# I2C-NIXIE-CTRL.net
KiCad netlist of a schematic drawn in Altium Designer
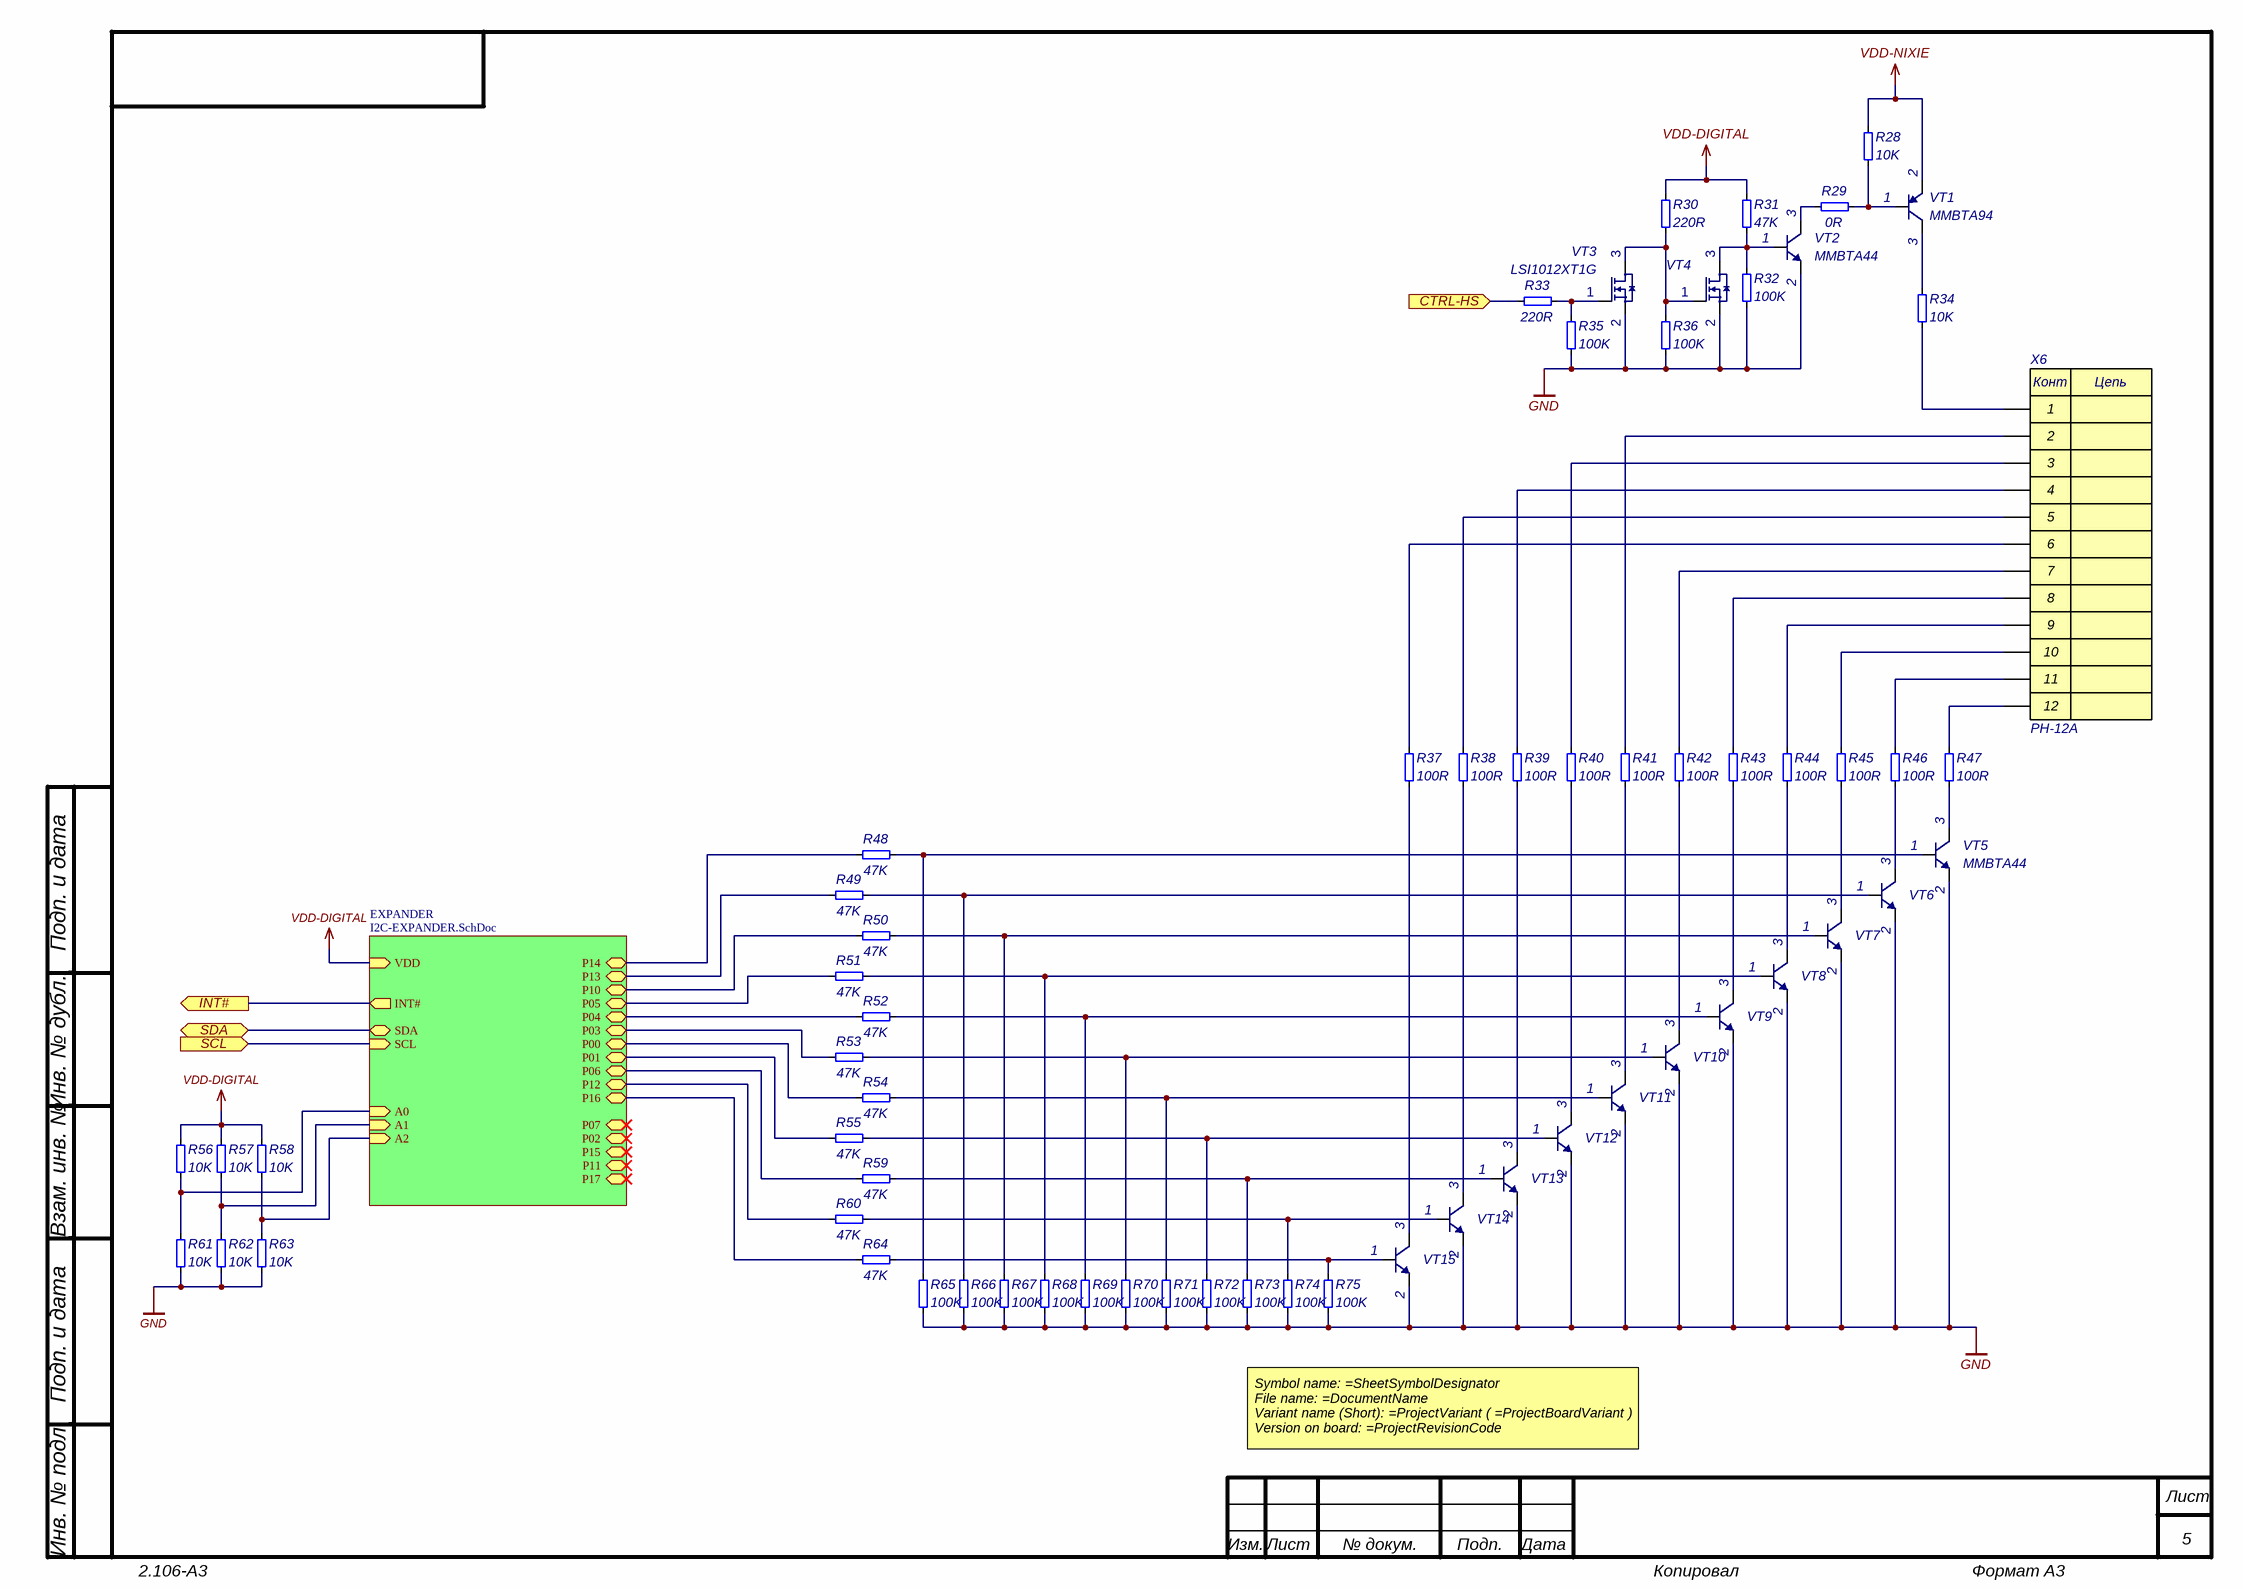
[diagram p0: I2C-NIXIE-CTRL.SchDoc]

(export (version "E")
  (design (tool "Eeschema 10.0.6"))
  (components
    (comp (ref "R28")
      (value "10K")
      (footprint "R_0805")
      (fields
        (field (name "PART NUMBER") "0805-0.125W-10K-200ppm±1%")
        (field (name "TOLERANCE") "1%")
        (field (name "MANUFACTURER") "Yageo")
      )
      (libsource (lib "ATB") (part "R"))
    )
    (comp (ref "R29")
      (value "0R")
      (footprint "R_0805")
      (fields
        (field (name "PART NUMBER") "0805-0.125W-0R-250ppm±5%")
        (field (name "TOLERANCE") "5%")
        (field (name "MANUFACTURER") "Yageo")
      )
      (libsource (lib "ATB") (part "R"))
    )
    (comp (ref "R30")
      (value "220R")
      (footprint "R_0402")
      (fields
        (field (name "PART NUMBER") "0402-0.0625W-220R-100ppm±1%")
        (field (name "TOLERANCE") "1%")
        (field (name "MANUFACTURER") "Yageo")
      )
      (libsource (lib "ATB") (part "R"))
    )
    (comp (ref "R31")
      (value "47K")
      (footprint "R_0402")
      (fields
        (field (name "PART NUMBER") "0402-0.0625W-47K-100ppm±1%")
        (field (name "TOLERANCE") "1%")
        (field (name "MANUFACTURER") "Yageo")
      )
      (libsource (lib "ATB") (part "R"))
    )
    (comp (ref "R32")
      (value "100K")
      (footprint "R_0402")
      (fields
        (field (name "PART NUMBER") "0402-0.0625W-100K-100ppm±1%")
        (field (name "TOLERANCE") "1%")
        (field (name "MANUFACTURER") "Yageo")
      )
      (libsource (lib "ATB") (part "R"))
    )
    (comp (ref "R33")
      (value "220R")
      (footprint "R_0402")
      (fields
        (field (name "PART NUMBER") "0402-0.0625W-220R-100ppm±1%")
        (field (name "TOLERANCE") "1%")
        (field (name "MANUFACTURER") "Yageo")
      )
      (libsource (lib "ATB") (part "R"))
    )
    (comp (ref "R34")
      (value "10K")
      (footprint "R_0805")
      (fields
        (field (name "PART NUMBER") "0805-0.125W-10K-200ppm±1%")
        (field (name "TOLERANCE") "1%")
        (field (name "MANUFACTURER") "Yageo")
      )
      (libsource (lib "ATB") (part "R"))
    )
    (comp (ref "R35")
      (value "100K")
      (footprint "R_0402")
      (fields
        (field (name "PART NUMBER") "0402-0.0625W-100K-100ppm±1%")
        (field (name "TOLERANCE") "1%")
        (field (name "MANUFACTURER") "Yageo")
      )
      (libsource (lib "ATB") (part "R"))
    )
    (comp (ref "R36")
      (value "100K")
      (footprint "R_0402")
      (fields
        (field (name "PART NUMBER") "0402-0.0625W-100K-100ppm±1%")
        (field (name "TOLERANCE") "1%")
        (field (name "MANUFACTURER") "Yageo")
      )
      (libsource (lib "ATB") (part "R"))
    )
    (comp (ref "R37")
      (value "100R")
      (footprint "R_0805")
      (fields
        (field (name "PART NUMBER") "0805-0.125W-100R-100ppm±1%")
        (field (name "TOLERANCE") "1%")
        (field (name "MANUFACTURER") "Yageo")
      )
      (libsource (lib "ATB") (part "R"))
    )
    (comp (ref "R38")
      (value "100R")
      (footprint "R_0805")
      (fields
        (field (name "PART NUMBER") "0805-0.125W-100R-100ppm±1%")
        (field (name "TOLERANCE") "1%")
        (field (name "MANUFACTURER") "Yageo")
      )
      (libsource (lib "ATB") (part "R"))
    )
    (comp (ref "R39")
      (value "100R")
      (footprint "R_0805")
      (fields
        (field (name "PART NUMBER") "0805-0.125W-100R-100ppm±1%")
        (field (name "TOLERANCE") "1%")
        (field (name "MANUFACTURER") "Yageo")
      )
      (libsource (lib "ATB") (part "R"))
    )
    (comp (ref "R40")
      (value "100R")
      (footprint "R_0805")
      (fields
        (field (name "PART NUMBER") "0805-0.125W-100R-100ppm±1%")
        (field (name "TOLERANCE") "1%")
        (field (name "MANUFACTURER") "Yageo")
      )
      (libsource (lib "ATB") (part "R"))
    )
    (comp (ref "R41")
      (value "100R")
      (footprint "R_0805")
      (fields
        (field (name "PART NUMBER") "0805-0.125W-100R-100ppm±1%")
        (field (name "TOLERANCE") "1%")
        (field (name "MANUFACTURER") "Yageo")
      )
      (libsource (lib "ATB") (part "R"))
    )
    (comp (ref "R42")
      (value "100R")
      (footprint "R_0805")
      (fields
        (field (name "PART NUMBER") "0805-0.125W-100R-100ppm±1%")
        (field (name "TOLERANCE") "1%")
        (field (name "MANUFACTURER") "Yageo")
      )
      (libsource (lib "ATB") (part "R"))
    )
    (comp (ref "R43")
      (value "100R")
      (footprint "R_0805")
      (fields
        (field (name "PART NUMBER") "0805-0.125W-100R-100ppm±1%")
        (field (name "TOLERANCE") "1%")
        (field (name "MANUFACTURER") "Yageo")
      )
      (libsource (lib "ATB") (part "R"))
    )
    (comp (ref "R44")
      (value "100R")
      (footprint "R_0805")
      (fields
        (field (name "PART NUMBER") "0805-0.125W-100R-100ppm±1%")
        (field (name "TOLERANCE") "1%")
        (field (name "MANUFACTURER") "Yageo")
      )
      (libsource (lib "ATB") (part "R"))
    )
    (comp (ref "R45")
      (value "100R")
      (footprint "R_0805")
      (fields
        (field (name "PART NUMBER") "0805-0.125W-100R-100ppm±1%")
        (field (name "TOLERANCE") "1%")
        (field (name "MANUFACTURER") "Yageo")
      )
      (libsource (lib "ATB") (part "R"))
    )
    (comp (ref "R46")
      (value "100R")
      (footprint "R_0805")
      (fields
        (field (name "PART NUMBER") "0805-0.125W-100R-100ppm±1%")
        (field (name "TOLERANCE") "1%")
        (field (name "MANUFACTURER") "Yageo")
      )
      (libsource (lib "ATB") (part "R"))
    )
    (comp (ref "R47")
      (value "100R")
      (footprint "R_0805")
      (fields
        (field (name "PART NUMBER") "0805-0.125W-100R-100ppm±1%")
        (field (name "TOLERANCE") "1%")
        (field (name "MANUFACTURER") "Yageo")
      )
      (libsource (lib "ATB") (part "R"))
    )
    (comp (ref "R48")
      (value "47K")
      (footprint "R_0402")
      (fields
        (field (name "PART NUMBER") "0402-0.0625W-47K-100ppm±1%")
        (field (name "TOLERANCE") "1%")
        (field (name "MANUFACTURER") "Yageo")
      )
      (libsource (lib "ATB") (part "R"))
    )
    (comp (ref "R49")
      (value "47K")
      (footprint "R_0402")
      (fields
        (field (name "PART NUMBER") "0402-0.0625W-47K-100ppm±1%")
        (field (name "TOLERANCE") "1%")
        (field (name "MANUFACTURER") "Yageo")
      )
      (libsource (lib "ATB") (part "R"))
    )
    (comp (ref "R50")
      (value "47K")
      (footprint "R_0402")
      (fields
        (field (name "PART NUMBER") "0402-0.0625W-47K-100ppm±1%")
        (field (name "TOLERANCE") "1%")
        (field (name "MANUFACTURER") "Yageo")
      )
      (libsource (lib "ATB") (part "R"))
    )
    (comp (ref "R51")
      (value "47K")
      (footprint "R_0402")
      (fields
        (field (name "PART NUMBER") "0402-0.0625W-47K-100ppm±1%")
        (field (name "TOLERANCE") "1%")
        (field (name "MANUFACTURER") "Yageo")
      )
      (libsource (lib "ATB") (part "R"))
    )
    (comp (ref "R52")
      (value "47K")
      (footprint "R_0402")
      (fields
        (field (name "PART NUMBER") "0402-0.0625W-47K-100ppm±1%")
        (field (name "TOLERANCE") "1%")
        (field (name "MANUFACTURER") "Yageo")
      )
      (libsource (lib "ATB") (part "R"))
    )
    (comp (ref "R53")
      (value "47K")
      (footprint "R_0402")
      (fields
        (field (name "PART NUMBER") "0402-0.0625W-47K-100ppm±1%")
        (field (name "TOLERANCE") "1%")
        (field (name "MANUFACTURER") "Yageo")
      )
      (libsource (lib "ATB") (part "R"))
    )
    (comp (ref "R54")
      (value "47K")
      (footprint "R_0402")
      (fields
        (field (name "PART NUMBER") "0402-0.0625W-47K-100ppm±1%")
        (field (name "TOLERANCE") "1%")
        (field (name "MANUFACTURER") "Yageo")
      )
      (libsource (lib "ATB") (part "R"))
    )
    (comp (ref "R55")
      (value "47K")
      (footprint "R_0402")
      (fields
        (field (name "PART NUMBER") "0402-0.0625W-47K-100ppm±1%")
        (field (name "TOLERANCE") "1%")
        (field (name "MANUFACTURER") "Yageo")
      )
      (libsource (lib "ATB") (part "R"))
    )
    (comp (ref "R56")
      (value "10K")
      (footprint "R_0402")
      (fields
        (field (name "PART NUMBER") "0402-0.0625W-10K-100ppm±1%")
        (field (name "TOLERANCE") "1%")
        (field (name "MANUFACTURER") "Yageo")
      )
      (libsource (lib "") (part "R_1"))
    )
    (comp (ref "R57")
      (value "10K")
      (footprint "R_0402")
      (fields
        (field (name "PART NUMBER") "0402-0.0625W-10K-100ppm±1%")
        (field (name "TOLERANCE") "1%")
        (field (name "MANUFACTURER") "Yageo")
      )
      (libsource (lib "") (part "R_1"))
    )
    (comp (ref "R58")
      (value "10K")
      (footprint "R_0402")
      (fields
        (field (name "PART NUMBER") "0402-0.0625W-10K-100ppm±1%")
        (field (name "TOLERANCE") "1%")
        (field (name "MANUFACTURER") "Yageo")
      )
      (libsource (lib "") (part "R_1"))
    )
    (comp (ref "R59")
      (value "47K")
      (footprint "R_0402")
      (fields
        (field (name "PART NUMBER") "0402-0.0625W-47K-100ppm±1%")
        (field (name "TOLERANCE") "1%")
        (field (name "MANUFACTURER") "Yageo")
      )
      (libsource (lib "ATB") (part "R"))
    )
    (comp (ref "R60")
      (value "47K")
      (footprint "R_0402")
      (fields
        (field (name "PART NUMBER") "0402-0.0625W-47K-100ppm±1%")
        (field (name "TOLERANCE") "1%")
        (field (name "MANUFACTURER") "Yageo")
      )
      (libsource (lib "ATB") (part "R"))
    )
    (comp (ref "R61")
      (value "10K")
      (footprint "R_0402")
      (fields
        (field (name "PART NUMBER") "0402-0.0625W-10K-100ppm±1%")
        (field (name "TOLERANCE") "1%")
        (field (name "MANUFACTURER") "Yageo")
      )
      (libsource (lib "") (part "R_1"))
    )
    (comp (ref "R62")
      (value "10K")
      (footprint "R_0402")
      (fields
        (field (name "PART NUMBER") "0402-0.0625W-10K-100ppm±1%")
        (field (name "TOLERANCE") "1%")
        (field (name "MANUFACTURER") "Yageo")
      )
      (libsource (lib "") (part "R_1"))
    )
    (comp (ref "R63")
      (value "10K")
      (footprint "R_0402")
      (fields
        (field (name "PART NUMBER") "0402-0.0625W-10K-100ppm±1%")
        (field (name "TOLERANCE") "1%")
        (field (name "MANUFACTURER") "Yageo")
      )
      (libsource (lib "") (part "R_1"))
    )
    (comp (ref "R64")
      (value "47K")
      (footprint "R_0402")
      (fields
        (field (name "PART NUMBER") "0402-0.0625W-47K-100ppm±1%")
        (field (name "TOLERANCE") "1%")
        (field (name "MANUFACTURER") "Yageo")
      )
      (libsource (lib "ATB") (part "R"))
    )
    (comp (ref "R65")
      (value "100K")
      (footprint "R_0402")
      (fields
        (field (name "PART NUMBER") "0402-0.0625W-100K-100ppm±1%")
        (field (name "TOLERANCE") "1%")
        (field (name "MANUFACTURER") "Yageo")
      )
      (libsource (lib "ATB") (part "R"))
    )
    (comp (ref "R66")
      (value "100K")
      (footprint "R_0402")
      (fields
        (field (name "PART NUMBER") "0402-0.0625W-100K-100ppm±1%")
        (field (name "TOLERANCE") "1%")
        (field (name "MANUFACTURER") "Yageo")
      )
      (libsource (lib "ATB") (part "R"))
    )
    (comp (ref "R67")
      (value "100K")
      (footprint "R_0402")
      (fields
        (field (name "PART NUMBER") "0402-0.0625W-100K-100ppm±1%")
        (field (name "TOLERANCE") "1%")
        (field (name "MANUFACTURER") "Yageo")
      )
      (libsource (lib "ATB") (part "R"))
    )
    (comp (ref "R68")
      (value "100K")
      (footprint "R_0402")
      (fields
        (field (name "PART NUMBER") "0402-0.0625W-100K-100ppm±1%")
        (field (name "TOLERANCE") "1%")
        (field (name "MANUFACTURER") "Yageo")
      )
      (libsource (lib "ATB") (part "R"))
    )
    (comp (ref "R69")
      (value "100K")
      (footprint "R_0402")
      (fields
        (field (name "PART NUMBER") "0402-0.0625W-100K-100ppm±1%")
        (field (name "TOLERANCE") "1%")
        (field (name "MANUFACTURER") "Yageo")
      )
      (libsource (lib "ATB") (part "R"))
    )
    (comp (ref "R70")
      (value "100K")
      (footprint "R_0402")
      (fields
        (field (name "PART NUMBER") "0402-0.0625W-100K-100ppm±1%")
        (field (name "TOLERANCE") "1%")
        (field (name "MANUFACTURER") "Yageo")
      )
      (libsource (lib "ATB") (part "R"))
    )
    (comp (ref "R71")
      (value "100K")
      (footprint "R_0402")
      (fields
        (field (name "PART NUMBER") "0402-0.0625W-100K-100ppm±1%")
        (field (name "TOLERANCE") "1%")
        (field (name "MANUFACTURER") "Yageo")
      )
      (libsource (lib "ATB") (part "R"))
    )
    (comp (ref "R72")
      (value "100K")
      (footprint "R_0402")
      (fields
        (field (name "PART NUMBER") "0402-0.0625W-100K-100ppm±1%")
        (field (name "TOLERANCE") "1%")
        (field (name "MANUFACTURER") "Yageo")
      )
      (libsource (lib "ATB") (part "R"))
    )
    (comp (ref "R73")
      (value "100K")
      (footprint "R_0402")
      (fields
        (field (name "PART NUMBER") "0402-0.0625W-100K-100ppm±1%")
        (field (name "TOLERANCE") "1%")
        (field (name "MANUFACTURER") "Yageo")
      )
      (libsource (lib "ATB") (part "R"))
    )
    (comp (ref "R74")
      (value "100K")
      (footprint "R_0402")
      (fields
        (field (name "PART NUMBER") "0402-0.0625W-100K-100ppm±1%")
        (field (name "TOLERANCE") "1%")
        (field (name "MANUFACTURER") "Yageo")
      )
      (libsource (lib "ATB") (part "R"))
    )
    (comp (ref "R75")
      (value "100K")
      (footprint "R_0402")
      (fields
        (field (name "PART NUMBER") "0402-0.0625W-100K-100ppm±1%")
        (field (name "TOLERANCE") "1%")
        (field (name "MANUFACTURER") "Yageo")
      )
      (libsource (lib "ATB") (part "R"))
    )
    (comp (ref "VT1")
      (value "MMBTA94")
      (footprint "SOT23")
      (description "400V 350mW 300mA PNP SOT-23 Bipolar Transistor")
      (fields (field (name "VOLTAGE") "400V") (field (name "MANUFACTURER") "PJSEMI"))
      (libsource (lib "ATB") (part "PNP"))
    )
    (comp (ref "VT2")
      (value "MMBTA44")
      (footprint "SOT23")
      (description "400V 350mW 300mA NPN SOT-23 Bipolar Transistor")
      (fields (field (name "VOLTAGE") "400V") (field (name "MANUFACTURER") "PJSEMI"))
      (libsource (lib "ATB") (part "NPN"))
    )
    (comp (ref "VT3")
      (value "LSI1012XT1G")
      (footprint "SC-89")
      (description "20V 500mA 250mW, 900mV@250uA N Channel SC-89 MOSFET")
      (fields (field (name "VOLTAGE") "20V") (field (name "MANUFACTURER") "LRC"))
      (libsource (lib "ATB") (part "MOSFET-N"))
    )
    (comp (ref "VT4")
      (value "LSI1012XT1G")
      (footprint "SC-89")
      (description "20V 500mA 250mW, 900mV@250uA N Channel SC-89 MOSFET")
      (fields (field (name "VOLTAGE") "20V") (field (name "MANUFACTURER") "LRC"))
      (libsource (lib "ATB") (part "MOSFET-N"))
    )
    (comp (ref "VT5")
      (value "MMBTA44")
      (footprint "SOT23")
      (description "400V 350mW 300mA NPN SOT-23 Bipolar Transistor")
      (fields (field (name "VOLTAGE") "400V") (field (name "MANUFACTURER") "PJSEMI"))
      (libsource (lib "ATB") (part "NPN"))
    )
    (comp (ref "VT6")
      (value "MMBTA44")
      (footprint "SOT23")
      (description "400V 350mW 300mA NPN SOT-23 Bipolar Transistor")
      (fields (field (name "VOLTAGE") "400V") (field (name "MANUFACTURER") "PJSEMI"))
      (libsource (lib "ATB") (part "NPN"))
    )
    (comp (ref "VT7")
      (value "MMBTA44")
      (footprint "SOT23")
      (description "400V 350mW 300mA NPN SOT-23 Bipolar Transistor")
      (fields (field (name "VOLTAGE") "400V") (field (name "MANUFACTURER") "PJSEMI"))
      (libsource (lib "ATB") (part "NPN"))
    )
    (comp (ref "VT8")
      (value "MMBTA44")
      (footprint "SOT23")
      (description "400V 350mW 300mA NPN SOT-23 Bipolar Transistor")
      (fields (field (name "VOLTAGE") "400V") (field (name "MANUFACTURER") "PJSEMI"))
      (libsource (lib "ATB") (part "NPN"))
    )
    (comp (ref "VT9")
      (value "MMBTA44")
      (footprint "SOT23")
      (description "400V 350mW 300mA NPN SOT-23 Bipolar Transistor")
      (fields (field (name "VOLTAGE") "400V") (field (name "MANUFACTURER") "PJSEMI"))
      (libsource (lib "ATB") (part "NPN"))
    )
    (comp (ref "VT10")
      (value "MMBTA44")
      (footprint "SOT23")
      (description "400V 350mW 300mA NPN SOT-23 Bipolar Transistor")
      (fields (field (name "VOLTAGE") "400V") (field (name "MANUFACTURER") "PJSEMI"))
      (libsource (lib "ATB") (part "NPN"))
    )
    (comp (ref "VT11")
      (value "MMBTA44")
      (footprint "SOT23")
      (description "400V 350mW 300mA NPN SOT-23 Bipolar Transistor")
      (fields (field (name "VOLTAGE") "400V") (field (name "MANUFACTURER") "PJSEMI"))
      (libsource (lib "ATB") (part "NPN"))
    )
    (comp (ref "VT12")
      (value "MMBTA44")
      (footprint "SOT23")
      (description "400V 350mW 300mA NPN SOT-23 Bipolar Transistor")
      (fields (field (name "VOLTAGE") "400V") (field (name "MANUFACTURER") "PJSEMI"))
      (libsource (lib "ATB") (part "NPN"))
    )
    (comp (ref "VT13")
      (value "MMBTA44")
      (footprint "SOT23")
      (description "400V 350mW 300mA NPN SOT-23 Bipolar Transistor")
      (fields (field (name "VOLTAGE") "400V") (field (name "MANUFACTURER") "PJSEMI"))
      (libsource (lib "ATB") (part "NPN"))
    )
    (comp (ref "VT14")
      (value "MMBTA44")
      (footprint "SOT23")
      (description "400V 350mW 300mA NPN SOT-23 Bipolar Transistor")
      (fields (field (name "VOLTAGE") "400V") (field (name "MANUFACTURER") "PJSEMI"))
      (libsource (lib "ATB") (part "NPN"))
    )
    (comp (ref "VT15")
      (value "MMBTA44")
      (footprint "SOT23")
      (description "400V 350mW 300mA NPN SOT-23 Bipolar Transistor")
      (fields (field (name "VOLTAGE") "400V") (field (name "MANUFACTURER") "PJSEMI"))
      (libsource (lib "ATB") (part "NPN"))
    )
    (comp (ref "X6")
      (value "PH-12A")
      (footprint "PH-12A")
      (description "12P PH 2mm 3A Straight P=2mm")
      (fields (field (name "MANUFACTURER") "HCTL"))
      (libsource (lib "ATB") (part "H12"))
    )
  )
  (nets
    (net (code "1") (name "/A0") (class "Default")
      (node (ref "R56") (pin "1") (pinfunction "1_1") (pintype "passive"))
      (node (ref "R61") (pin "2") (pinfunction "2_2") (pintype "passive"))
    )
    (net (code "2") (name "/A1") (class "Default")
      (node (ref "R57") (pin "1") (pinfunction "1_1") (pintype "passive"))
      (node (ref "R62") (pin "2") (pinfunction "2_2") (pintype "passive"))
    )
    (net (code "3") (name "/A2") (class "Default")
      (node (ref "R58") (pin "1") (pinfunction "1_1") (pintype "passive"))
      (node (ref "R63") (pin "2") (pinfunction "2_2") (pintype "passive"))
    )
    (net (code "4") (name "/CTRL-HS") (class "Default")
      (node (ref "R33") (pin "1") (pinfunction "1_1") (pintype "passive"))
    )
    (net (code "6") (name "/P00") (class "Default")
      (node (ref "R54") (pin "1") (pinfunction "1_1") (pintype "passive"))
    )
    (net (code "7") (name "/P01") (class "Default")
      (node (ref "R55") (pin "1") (pinfunction "1_1") (pintype "passive"))
    )
    (net (code "9") (name "/P03") (class "Default")
      (node (ref "R53") (pin "1") (pinfunction "1_1") (pintype "passive"))
    )
    (net (code "10") (name "/P04") (class "Default")
      (node (ref "R52") (pin "1") (pinfunction "1_1") (pintype "passive"))
    )
    (net (code "11") (name "/P05") (class "Default")
      (node (ref "R51") (pin "1") (pinfunction "1_1") (pintype "passive"))
    )
    (net (code "12") (name "/P06") (class "Default")
      (node (ref "R59") (pin "1") (pinfunction "1_1") (pintype "passive"))
    )
    (net (code "14") (name "/P10") (class "Default")
      (node (ref "R50") (pin "1") (pinfunction "1_1") (pintype "passive"))
    )
    (net (code "16") (name "/P12") (class "Default")
      (node (ref "R60") (pin "1") (pinfunction "1_1") (pintype "passive"))
    )
    (net (code "17") (name "/P13") (class "Default")
      (node (ref "R49") (pin "1") (pinfunction "1_1") (pintype "passive"))
    )
    (net (code "18") (name "/P14") (class "Default")
      (node (ref "R48") (pin "1") (pinfunction "1_1") (pintype "passive"))
    )
    (net (code "20") (name "/P16") (class "Default")
      (node (ref "R64") (pin "1") (pinfunction "1_1") (pintype "passive"))
    )
    (net (code "24") (name "GND") (class "Default")
      (node (ref "R32") (pin "2") (pinfunction "2_2") (pintype "passive"))
      (node (ref "R35") (pin "2") (pinfunction "2_2") (pintype "passive"))
      (node (ref "R36") (pin "2") (pinfunction "2_2") (pintype "passive"))
      (node (ref "R61") (pin "1") (pinfunction "1_1") (pintype "passive"))
      (node (ref "R62") (pin "1") (pinfunction "1_1") (pintype "passive"))
      (node (ref "R63") (pin "1") (pinfunction "1_1") (pintype "passive"))
      (node (ref "R65") (pin "2") (pinfunction "2_2") (pintype "passive"))
      (node (ref "R66") (pin "2") (pinfunction "2_2") (pintype "passive"))
      (node (ref "R67") (pin "2") (pinfunction "2_2") (pintype "passive"))
      (node (ref "R68") (pin "2") (pinfunction "2_2") (pintype "passive"))
      (node (ref "R69") (pin "2") (pinfunction "2_2") (pintype "passive"))
      (node (ref "R70") (pin "2") (pinfunction "2_2") (pintype "passive"))
      (node (ref "R71") (pin "2") (pinfunction "2_2") (pintype "passive"))
      (node (ref "R72") (pin "2") (pinfunction "2_2") (pintype "passive"))
      (node (ref "R73") (pin "2") (pinfunction "2_2") (pintype "passive"))
      (node (ref "R74") (pin "2") (pinfunction "2_2") (pintype "passive"))
      (node (ref "R75") (pin "2") (pinfunction "2_2") (pintype "passive"))
      (node (ref "VT10") (pin "2") (pinfunction "E_2") (pintype "passive"))
      (node (ref "VT11") (pin "2") (pinfunction "E_2") (pintype "passive"))
      (node (ref "VT12") (pin "2") (pinfunction "E_2") (pintype "passive"))
      (node (ref "VT13") (pin "2") (pinfunction "E_2") (pintype "passive"))
      (node (ref "VT14") (pin "2") (pinfunction "E_2") (pintype "passive"))
      (node (ref "VT15") (pin "2") (pinfunction "E_2") (pintype "passive"))
      (node (ref "VT2") (pin "2") (pinfunction "E_2") (pintype "passive"))
      (node (ref "VT3") (pin "2") (pinfunction "S_2") (pintype "passive"))
      (node (ref "VT4") (pin "2") (pinfunction "S_2") (pintype "passive"))
      (node (ref "VT5") (pin "2") (pinfunction "E_2") (pintype "passive"))
      (node (ref "VT6") (pin "2") (pinfunction "E_2") (pintype "passive"))
      (node (ref "VT7") (pin "2") (pinfunction "E_2") (pintype "passive"))
      (node (ref "VT8") (pin "2") (pinfunction "E_2") (pintype "passive"))
      (node (ref "VT9") (pin "2") (pinfunction "E_2") (pintype "passive"))
    )
    (net (code "25") (name "Net-(R34-Pad2)") (class "Default")
      (node (ref "R34") (pin "2") (pinfunction "2_2") (pintype "passive"))
      (node (ref "X6") (pin "1") (pinfunction "1_1") (pintype "passive"))
    )
    (net (code "26") (name "Net-(R37-Pad1)") (class "Default")
      (node (ref "R37") (pin "1") (pinfunction "1_1") (pintype "passive"))
      (node (ref "X6") (pin "6") (pinfunction "6_6") (pintype "passive"))
    )
    (net (code "27") (name "Net-(R38-Pad1)") (class "Default")
      (node (ref "R38") (pin "1") (pinfunction "1_1") (pintype "passive"))
      (node (ref "X6") (pin "5") (pinfunction "5_5") (pintype "passive"))
    )
    (net (code "28") (name "Net-(R39-Pad1)") (class "Default")
      (node (ref "R39") (pin "1") (pinfunction "1_1") (pintype "passive"))
      (node (ref "X6") (pin "4") (pinfunction "4_4") (pintype "passive"))
    )
    (net (code "29") (name "Net-(R40-Pad1)") (class "Default")
      (node (ref "R40") (pin "1") (pinfunction "1_1") (pintype "passive"))
      (node (ref "X6") (pin "3") (pinfunction "3_3") (pintype "passive"))
    )
    (net (code "30") (name "Net-(R41-Pad1)") (class "Default")
      (node (ref "R41") (pin "1") (pinfunction "1_1") (pintype "passive"))
      (node (ref "X6") (pin "2") (pinfunction "2_2") (pintype "passive"))
    )
    (net (code "31") (name "Net-(R42-Pad1)") (class "Default")
      (node (ref "R42") (pin "1") (pinfunction "1_1") (pintype "passive"))
      (node (ref "X6") (pin "7") (pinfunction "7_7") (pintype "passive"))
    )
    (net (code "32") (name "Net-(R43-Pad1)") (class "Default")
      (node (ref "R43") (pin "1") (pinfunction "1_1") (pintype "passive"))
      (node (ref "X6") (pin "8") (pinfunction "8_8") (pintype "passive"))
    )
    (net (code "33") (name "Net-(R44-Pad1)") (class "Default")
      (node (ref "R44") (pin "1") (pinfunction "1_1") (pintype "passive"))
      (node (ref "X6") (pin "9") (pinfunction "9_9") (pintype "passive"))
    )
    (net (code "34") (name "Net-(R45-Pad1)") (class "Default")
      (node (ref "R45") (pin "1") (pinfunction "1_1") (pintype "passive"))
      (node (ref "X6") (pin "10") (pinfunction "10_10") (pintype "passive"))
    )
    (net (code "35") (name "Net-(R46-Pad1)") (class "Default")
      (node (ref "R46") (pin "1") (pinfunction "1_1") (pintype "passive"))
      (node (ref "X6") (pin "11") (pinfunction "11_11") (pintype "passive"))
    )
    (net (code "36") (name "Net-(R47-Pad1)") (class "Default")
      (node (ref "R47") (pin "1") (pinfunction "1_1") (pintype "passive"))
      (node (ref "X6") (pin "12") (pinfunction "12_12") (pintype "passive"))
    )
    (net (code "37") (name "Net-(VT1-B)") (class "Default")
      (node (ref "R28") (pin "2") (pinfunction "2_2") (pintype "passive"))
      (node (ref "R29") (pin "2") (pinfunction "2_2") (pintype "passive"))
      (node (ref "VT1") (pin "1") (pinfunction "B_1") (pintype "passive"))
    )
    (net (code "38") (name "Net-(VT1-C)") (class "Default")
      (node (ref "R34") (pin "1") (pinfunction "1_1") (pintype "passive"))
      (node (ref "VT1") (pin "3") (pinfunction "C_3") (pintype "passive"))
    )
    (net (code "39") (name "Net-(VT2-B)") (class "Default")
      (node (ref "R31") (pin "2") (pinfunction "2_2") (pintype "passive"))
      (node (ref "R32") (pin "1") (pinfunction "1_1") (pintype "passive"))
      (node (ref "VT2") (pin "1") (pinfunction "B_1") (pintype "passive"))
      (node (ref "VT4") (pin "3") (pinfunction "D_3") (pintype "passive"))
    )
    (net (code "40") (name "Net-(VT2-C)") (class "Default")
      (node (ref "R29") (pin "1") (pinfunction "1_1") (pintype "passive"))
      (node (ref "VT2") (pin "3") (pinfunction "C_3") (pintype "passive"))
    )
    (net (code "41") (name "Net-(VT3-D)") (class "Default")
      (node (ref "R30") (pin "2") (pinfunction "2_2") (pintype "passive"))
      (node (ref "R36") (pin "1") (pinfunction "1_1") (pintype "passive"))
      (node (ref "VT3") (pin "3") (pinfunction "D_3") (pintype "passive"))
      (node (ref "VT4") (pin "1") (pinfunction "G_1") (pintype "passive"))
    )
    (net (code "42") (name "Net-(VT3-G)") (class "Default")
      (node (ref "R33") (pin "2") (pinfunction "2_2") (pintype "passive"))
      (node (ref "R35") (pin "1") (pinfunction "1_1") (pintype "passive"))
      (node (ref "VT3") (pin "1") (pinfunction "G_1") (pintype "passive"))
    )
    (net (code "43") (name "Net-(VT5-B)") (class "Default")
      (node (ref "R48") (pin "2") (pinfunction "2_2") (pintype "passive"))
      (node (ref "R65") (pin "1") (pinfunction "1_1") (pintype "passive"))
      (node (ref "VT5") (pin "1") (pinfunction "B_1") (pintype "passive"))
    )
    (net (code "44") (name "Net-(VT5-C)") (class "Default")
      (node (ref "R47") (pin "2") (pinfunction "2_2") (pintype "passive"))
      (node (ref "VT5") (pin "3") (pinfunction "C_3") (pintype "passive"))
    )
    (net (code "45") (name "Net-(VT6-B)") (class "Default")
      (node (ref "R49") (pin "2") (pinfunction "2_2") (pintype "passive"))
      (node (ref "R66") (pin "1") (pinfunction "1_1") (pintype "passive"))
      (node (ref "VT6") (pin "1") (pinfunction "B_1") (pintype "passive"))
    )
    (net (code "46") (name "Net-(VT6-C)") (class "Default")
      (node (ref "R46") (pin "2") (pinfunction "2_2") (pintype "passive"))
      (node (ref "VT6") (pin "3") (pinfunction "C_3") (pintype "passive"))
    )
    (net (code "47") (name "Net-(VT7-B)") (class "Default")
      (node (ref "R50") (pin "2") (pinfunction "2_2") (pintype "passive"))
      (node (ref "R67") (pin "1") (pinfunction "1_1") (pintype "passive"))
      (node (ref "VT7") (pin "1") (pinfunction "B_1") (pintype "passive"))
    )
    (net (code "48") (name "Net-(VT7-C)") (class "Default")
      (node (ref "R45") (pin "2") (pinfunction "2_2") (pintype "passive"))
      (node (ref "VT7") (pin "3") (pinfunction "C_3") (pintype "passive"))
    )
    (net (code "49") (name "Net-(VT8-B)") (class "Default")
      (node (ref "R51") (pin "2") (pinfunction "2_2") (pintype "passive"))
      (node (ref "R68") (pin "1") (pinfunction "1_1") (pintype "passive"))
      (node (ref "VT8") (pin "1") (pinfunction "B_1") (pintype "passive"))
    )
    (net (code "50") (name "Net-(VT8-C)") (class "Default")
      (node (ref "R44") (pin "2") (pinfunction "2_2") (pintype "passive"))
      (node (ref "VT8") (pin "3") (pinfunction "C_3") (pintype "passive"))
    )
    (net (code "51") (name "Net-(VT9-B)") (class "Default")
      (node (ref "R52") (pin "2") (pinfunction "2_2") (pintype "passive"))
      (node (ref "R69") (pin "1") (pinfunction "1_1") (pintype "passive"))
      (node (ref "VT9") (pin "1") (pinfunction "B_1") (pintype "passive"))
    )
    (net (code "52") (name "Net-(VT9-C)") (class "Default")
      (node (ref "R43") (pin "2") (pinfunction "2_2") (pintype "passive"))
      (node (ref "VT9") (pin "3") (pinfunction "C_3") (pintype "passive"))
    )
    (net (code "53") (name "Net-(VT10-B)") (class "Default")
      (node (ref "R53") (pin "2") (pinfunction "2_2") (pintype "passive"))
      (node (ref "R70") (pin "1") (pinfunction "1_1") (pintype "passive"))
      (node (ref "VT10") (pin "1") (pinfunction "B_1") (pintype "passive"))
    )
    (net (code "54") (name "Net-(VT10-C)") (class "Default")
      (node (ref "R42") (pin "2") (pinfunction "2_2") (pintype "passive"))
      (node (ref "VT10") (pin "3") (pinfunction "C_3") (pintype "passive"))
    )
    (net (code "55") (name "Net-(VT11-B)") (class "Default")
      (node (ref "R54") (pin "2") (pinfunction "2_2") (pintype "passive"))
      (node (ref "R71") (pin "1") (pinfunction "1_1") (pintype "passive"))
      (node (ref "VT11") (pin "1") (pinfunction "B_1") (pintype "passive"))
    )
    (net (code "56") (name "Net-(VT11-C)") (class "Default")
      (node (ref "R41") (pin "2") (pinfunction "2_2") (pintype "passive"))
      (node (ref "VT11") (pin "3") (pinfunction "C_3") (pintype "passive"))
    )
    (net (code "57") (name "Net-(VT12-B)") (class "Default")
      (node (ref "R55") (pin "2") (pinfunction "2_2") (pintype "passive"))
      (node (ref "R72") (pin "1") (pinfunction "1_1") (pintype "passive"))
      (node (ref "VT12") (pin "1") (pinfunction "B_1") (pintype "passive"))
    )
    (net (code "58") (name "Net-(VT12-C)") (class "Default")
      (node (ref "R40") (pin "2") (pinfunction "2_2") (pintype "passive"))
      (node (ref "VT12") (pin "3") (pinfunction "C_3") (pintype "passive"))
    )
    (net (code "59") (name "Net-(VT13-B)") (class "Default")
      (node (ref "R59") (pin "2") (pinfunction "2_2") (pintype "passive"))
      (node (ref "R73") (pin "1") (pinfunction "1_1") (pintype "passive"))
      (node (ref "VT13") (pin "1") (pinfunction "B_1") (pintype "passive"))
    )
    (net (code "60") (name "Net-(VT13-C)") (class "Default")
      (node (ref "R39") (pin "2") (pinfunction "2_2") (pintype "passive"))
      (node (ref "VT13") (pin "3") (pinfunction "C_3") (pintype "passive"))
    )
    (net (code "61") (name "Net-(VT14-B)") (class "Default")
      (node (ref "R60") (pin "2") (pinfunction "2_2") (pintype "passive"))
      (node (ref "R74") (pin "1") (pinfunction "1_1") (pintype "passive"))
      (node (ref "VT14") (pin "1") (pinfunction "B_1") (pintype "passive"))
    )
    (net (code "62") (name "Net-(VT14-C)") (class "Default")
      (node (ref "R38") (pin "2") (pinfunction "2_2") (pintype "passive"))
      (node (ref "VT14") (pin "3") (pinfunction "C_3") (pintype "passive"))
    )
    (net (code "63") (name "Net-(VT15-B)") (class "Default")
      (node (ref "R64") (pin "2") (pinfunction "2_2") (pintype "passive"))
      (node (ref "R75") (pin "1") (pinfunction "1_1") (pintype "passive"))
      (node (ref "VT15") (pin "1") (pinfunction "B_1") (pintype "passive"))
    )
    (net (code "64") (name "Net-(VT15-C)") (class "Default")
      (node (ref "R37") (pin "2") (pinfunction "2_2") (pintype "passive"))
      (node (ref "VT15") (pin "3") (pinfunction "C_3") (pintype "passive"))
    )
    (net (code "65") (name "VDD-DIGITAL") (class "Default")
      (node (ref "R30") (pin "1") (pinfunction "1_1") (pintype "passive"))
      (node (ref "R31") (pin "1") (pinfunction "1_1") (pintype "passive"))
      (node (ref "R56") (pin "2") (pinfunction "2_2") (pintype "passive"))
      (node (ref "R57") (pin "2") (pinfunction "2_2") (pintype "passive"))
      (node (ref "R58") (pin "2") (pinfunction "2_2") (pintype "passive"))
    )
    (net (code "66") (name "VDD-NIXIE") (class "Default")
      (node (ref "R28") (pin "1") (pinfunction "1_1") (pintype "passive"))
      (node (ref "VT1") (pin "2") (pinfunction "E_2") (pintype "passive"))
    )
  )
)
